# VDC.net
KiCad netlist of a schematic drawn in EAGLE
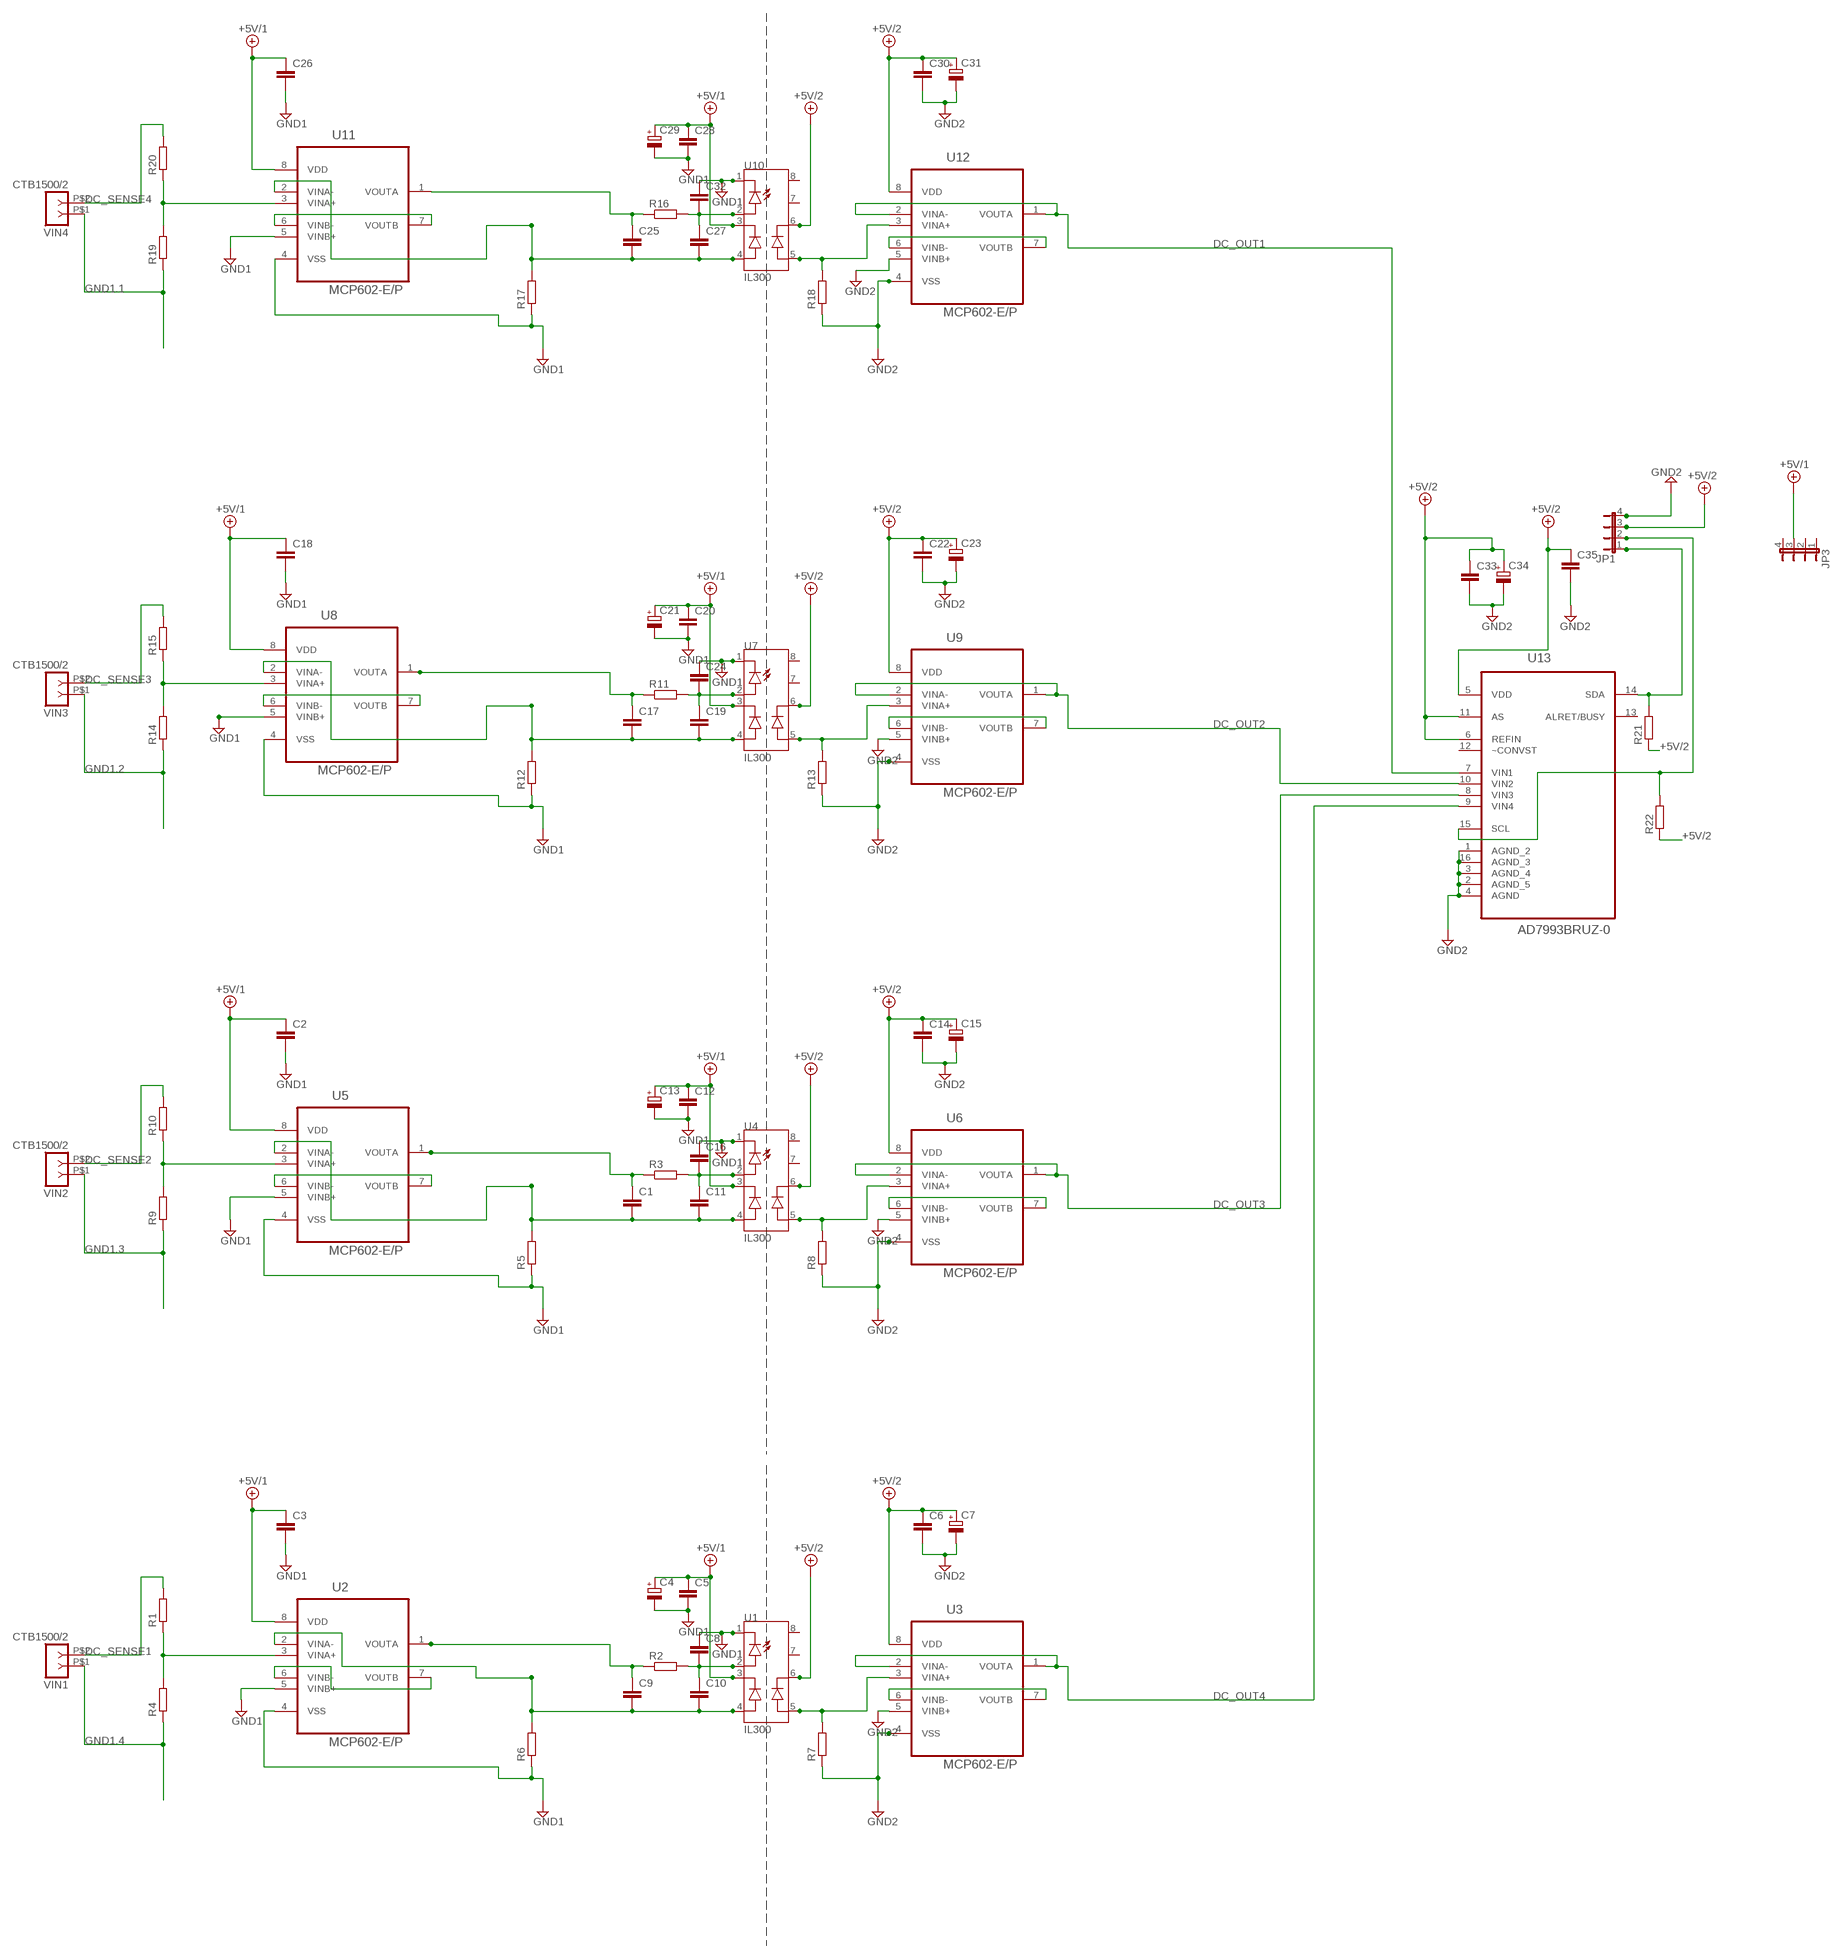
[diagram p0: schematic, sheet 1]

(export (version "E")
  (design (tool "Eeschema 10.0.6"))
  (components
    (comp (ref "C1")
      (value "C-EU025-040X050")
      (footprint "eagle-import:C025-040X050")
      (libsource (lib "eagle-import") (part "C-EU025-040X050"))
    )
    (comp (ref "C2")
      (value "C-EU025-040X050")
      (footprint "eagle-import:C025-040X050")
      (libsource (lib "eagle-import") (part "C-EU025-040X050"))
    )
    (comp (ref "C3")
      (value "C-EU025-040X050")
      (footprint "eagle-import:C025-040X050")
      (libsource (lib "eagle-import") (part "C-EU025-040X050"))
    )
    (comp (ref "C4")
      (value "CPOL-EUE2-5")
      (footprint "eagle-import:E2-5")
      (libsource (lib "eagle-import") (part "CPOL-EUE2-5"))
    )
    (comp (ref "C5")
      (value "C-EU025-040X050")
      (footprint "eagle-import:C025-040X050")
      (libsource (lib "eagle-import") (part "C-EU025-040X050"))
    )
    (comp (ref "C6")
      (value "C-EU025-040X050")
      (footprint "eagle-import:C025-040X050")
      (libsource (lib "eagle-import") (part "C-EU025-040X050"))
    )
    (comp (ref "C7")
      (value "CPOL-EUE2-5")
      (footprint "eagle-import:E2-5")
      (libsource (lib "eagle-import") (part "CPOL-EUE2-5"))
    )
    (comp (ref "C8")
      (value "C-EU025-040X050")
      (footprint "eagle-import:C025-040X050")
      (libsource (lib "eagle-import") (part "C-EU025-040X050"))
    )
    (comp (ref "C9")
      (value "C-EU025-040X050")
      (footprint "eagle-import:C025-040X050")
      (libsource (lib "eagle-import") (part "C-EU025-040X050"))
    )
    (comp (ref "C10")
      (value "C-EU025-040X050")
      (footprint "eagle-import:C025-040X050")
      (libsource (lib "eagle-import") (part "C-EU025-040X050"))
    )
    (comp (ref "C11")
      (value "C-EU025-040X050")
      (footprint "eagle-import:C025-040X050")
      (libsource (lib "eagle-import") (part "C-EU025-040X050"))
    )
    (comp (ref "C12")
      (value "C-EU025-040X050")
      (footprint "eagle-import:C025-040X050")
      (libsource (lib "eagle-import") (part "C-EU025-040X050"))
    )
    (comp (ref "C13")
      (value "CPOL-EUE2-5")
      (footprint "eagle-import:E2-5")
      (libsource (lib "eagle-import") (part "CPOL-EUE2-5"))
    )
    (comp (ref "C14")
      (value "C-EU025-040X050")
      (footprint "eagle-import:C025-040X050")
      (libsource (lib "eagle-import") (part "C-EU025-040X050"))
    )
    (comp (ref "C15")
      (value "CPOL-EUE2-5")
      (footprint "eagle-import:E2-5")
      (libsource (lib "eagle-import") (part "CPOL-EUE2-5"))
    )
    (comp (ref "C16")
      (value "C-EU025-040X050")
      (footprint "eagle-import:C025-040X050")
      (libsource (lib "eagle-import") (part "C-EU025-040X050"))
    )
    (comp (ref "C17")
      (value "C-EU025-040X050")
      (footprint "eagle-import:C025-040X050")
      (libsource (lib "eagle-import") (part "C-EU025-040X050"))
    )
    (comp (ref "C18")
      (value "C-EU025-040X050")
      (footprint "eagle-import:C025-040X050")
      (libsource (lib "eagle-import") (part "C-EU025-040X050"))
    )
    (comp (ref "C19")
      (value "C-EU025-040X050")
      (footprint "eagle-import:C025-040X050")
      (libsource (lib "eagle-import") (part "C-EU025-040X050"))
    )
    (comp (ref "C20")
      (value "C-EU025-040X050")
      (footprint "eagle-import:C025-040X050")
      (libsource (lib "eagle-import") (part "C-EU025-040X050"))
    )
    (comp (ref "C21")
      (value "CPOL-EUE2-5")
      (footprint "eagle-import:E2-5")
      (libsource (lib "eagle-import") (part "CPOL-EUE2-5"))
    )
    (comp (ref "C22")
      (value "C-EU025-040X050")
      (footprint "eagle-import:C025-040X050")
      (libsource (lib "eagle-import") (part "C-EU025-040X050"))
    )
    (comp (ref "C23")
      (value "CPOL-EUE2-5")
      (footprint "eagle-import:E2-5")
      (libsource (lib "eagle-import") (part "CPOL-EUE2-5"))
    )
    (comp (ref "C24")
      (value "C-EU025-040X050")
      (footprint "eagle-import:C025-040X050")
      (libsource (lib "eagle-import") (part "C-EU025-040X050"))
    )
    (comp (ref "C25")
      (value "C-EU025-040X050")
      (footprint "eagle-import:C025-040X050")
      (libsource (lib "eagle-import") (part "C-EU025-040X050"))
    )
    (comp (ref "C26")
      (value "C-EU025-040X050")
      (footprint "eagle-import:C025-040X050")
      (libsource (lib "eagle-import") (part "C-EU025-040X050"))
    )
    (comp (ref "C27")
      (value "C-EU025-040X050")
      (footprint "eagle-import:C025-040X050")
      (libsource (lib "eagle-import") (part "C-EU025-040X050"))
    )
    (comp (ref "C28")
      (value "C-EU025-040X050")
      (footprint "eagle-import:C025-040X050")
      (libsource (lib "eagle-import") (part "C-EU025-040X050"))
    )
    (comp (ref "C29")
      (value "CPOL-EUE2-5")
      (footprint "eagle-import:E2-5")
      (libsource (lib "eagle-import") (part "CPOL-EUE2-5"))
    )
    (comp (ref "C30")
      (value "C-EU025-040X050")
      (footprint "eagle-import:C025-040X050")
      (libsource (lib "eagle-import") (part "C-EU025-040X050"))
    )
    (comp (ref "C31")
      (value "CPOL-EUE2-5")
      (footprint "eagle-import:E2-5")
      (libsource (lib "eagle-import") (part "CPOL-EUE2-5"))
    )
    (comp (ref "C32")
      (value "C-EU025-040X050")
      (footprint "eagle-import:C025-040X050")
      (libsource (lib "eagle-import") (part "C-EU025-040X050"))
    )
    (comp (ref "C33")
      (value "C-EU025-024X044")
      (footprint "eagle-import:C025-024X044")
      (libsource (lib "eagle-import") (part "C-EU025-024X044"))
    )
    (comp (ref "C34")
      (value "CPOL-EUE2-4")
      (footprint "eagle-import:E2-4")
      (libsource (lib "eagle-import") (part "CPOL-EUE2-4"))
    )
    (comp (ref "C35")
      (value "C-EU025-025X050")
      (footprint "eagle-import:C025-025X050")
      (libsource (lib "eagle-import") (part "C-EU025-025X050"))
    )
    (comp (ref "JP1")
      (value "JP4E")
      (footprint "eagle-import:JP4")
      (libsource (lib "eagle-import") (part "JP4E"))
    )
    (comp (ref "JP3")
      (value "JP4E")
      (footprint "eagle-import:JP4")
      (libsource (lib "eagle-import") (part "JP4E"))
    )
    (comp (ref "R1")
      (value "R-EU_0207/10")
      (footprint "eagle-import:0207_10")
      (libsource (lib "eagle-import") (part "R-EU_0207/10"))
    )
    (comp (ref "R2")
      (value "R-EU_0207/10")
      (footprint "eagle-import:0207_10")
      (libsource (lib "eagle-import") (part "R-EU_0207/10"))
    )
    (comp (ref "R3")
      (value "R-EU_0207/10")
      (footprint "eagle-import:0207_10")
      (libsource (lib "eagle-import") (part "R-EU_0207/10"))
    )
    (comp (ref "R4")
      (value "R-EU_0207/10")
      (footprint "eagle-import:0207_10")
      (libsource (lib "eagle-import") (part "R-EU_0207/10"))
    )
    (comp (ref "R5")
      (value "R-EU_0207/10")
      (footprint "eagle-import:0207_10")
      (libsource (lib "eagle-import") (part "R-EU_0207/10"))
    )
    (comp (ref "R6")
      (value "R-EU_0207/10")
      (footprint "eagle-import:0207_10")
      (libsource (lib "eagle-import") (part "R-EU_0207/10"))
    )
    (comp (ref "R7")
      (value "R-EU_0207/10")
      (footprint "eagle-import:0207_10")
      (libsource (lib "eagle-import") (part "R-EU_0207/10"))
    )
    (comp (ref "R8")
      (value "R-EU_0207/10")
      (footprint "eagle-import:0207_10")
      (libsource (lib "eagle-import") (part "R-EU_0207/10"))
    )
    (comp (ref "R9")
      (value "R-EU_0207/10")
      (footprint "eagle-import:0207_10")
      (libsource (lib "eagle-import") (part "R-EU_0207/10"))
    )
    (comp (ref "R10")
      (value "R-EU_0207/10")
      (footprint "eagle-import:0207_10")
      (libsource (lib "eagle-import") (part "R-EU_0207/10"))
    )
    (comp (ref "R11")
      (value "R-EU_0207/10")
      (footprint "eagle-import:0207_10")
      (libsource (lib "eagle-import") (part "R-EU_0207/10"))
    )
    (comp (ref "R12")
      (value "R-EU_0207/10")
      (footprint "eagle-import:0207_10")
      (libsource (lib "eagle-import") (part "R-EU_0207/10"))
    )
    (comp (ref "R13")
      (value "R-EU_0207/10")
      (footprint "eagle-import:0207_10")
      (libsource (lib "eagle-import") (part "R-EU_0207/10"))
    )
    (comp (ref "R14")
      (value "R-EU_0207/10")
      (footprint "eagle-import:0207_10")
      (libsource (lib "eagle-import") (part "R-EU_0207/10"))
    )
    (comp (ref "R15")
      (value "R-EU_0207/10")
      (footprint "eagle-import:0207_10")
      (libsource (lib "eagle-import") (part "R-EU_0207/10"))
    )
    (comp (ref "R16")
      (value "R-EU_0207/10")
      (footprint "eagle-import:0207_10")
      (libsource (lib "eagle-import") (part "R-EU_0207/10"))
    )
    (comp (ref "R17")
      (value "R-EU_0207/10")
      (footprint "eagle-import:0207_10")
      (libsource (lib "eagle-import") (part "R-EU_0207/10"))
    )
    (comp (ref "R18")
      (value "R-EU_0207/10")
      (footprint "eagle-import:0207_10")
      (libsource (lib "eagle-import") (part "R-EU_0207/10"))
    )
    (comp (ref "R19")
      (value "R-EU_0207/10")
      (footprint "eagle-import:0207_10")
      (libsource (lib "eagle-import") (part "R-EU_0207/10"))
    )
    (comp (ref "R20")
      (value "R-EU_0207/10")
      (footprint "eagle-import:0207_10")
      (libsource (lib "eagle-import") (part "R-EU_0207/10"))
    )
    (comp (ref "R21")
      (value "R-EU_0207/10")
      (footprint "eagle-import:0207_10")
      (libsource (lib "eagle-import") (part "R-EU_0207/10"))
    )
    (comp (ref "R22")
      (value "R-EU_0207/10")
      (footprint "eagle-import:0207_10")
      (libsource (lib "eagle-import") (part "R-EU_0207/10"))
    )
    (comp (ref "U1")
      (value "IL300")
      (footprint "eagle-import:DIL08")
      (libsource (lib "eagle-import") (part "IL300"))
    )
    (comp (ref "U2")
      (value "MCP602-E/P")
      (footprint "eagle-import:DIP254P762X508-8P")
      (libsource (lib "eagle-import") (part "MCP602-E/P"))
    )
    (comp (ref "U3")
      (value "MCP602-E/P")
      (footprint "eagle-import:DIP254P762X508-8P")
      (libsource (lib "eagle-import") (part "MCP602-E/P"))
    )
    (comp (ref "U4")
      (value "IL300")
      (footprint "eagle-import:DIL08")
      (libsource (lib "eagle-import") (part "IL300"))
    )
    (comp (ref "U5")
      (value "MCP602-E/P")
      (footprint "eagle-import:DIP254P762X508-8P")
      (libsource (lib "eagle-import") (part "MCP602-E/P"))
    )
    (comp (ref "U6")
      (value "MCP602-E/P")
      (footprint "eagle-import:DIP254P762X508-8P")
      (libsource (lib "eagle-import") (part "MCP602-E/P"))
    )
    (comp (ref "U7")
      (value "IL300")
      (footprint "eagle-import:DIL08")
      (libsource (lib "eagle-import") (part "IL300"))
    )
    (comp (ref "U8")
      (value "MCP602-E/P")
      (footprint "eagle-import:DIP254P762X508-8P")
      (libsource (lib "eagle-import") (part "MCP602-E/P"))
    )
    (comp (ref "U9")
      (value "MCP602-E/P")
      (footprint "eagle-import:DIP254P762X508-8P")
      (libsource (lib "eagle-import") (part "MCP602-E/P"))
    )
    (comp (ref "U10")
      (value "IL300")
      (footprint "eagle-import:DIL08")
      (libsource (lib "eagle-import") (part "IL300"))
    )
    (comp (ref "U11")
      (value "MCP602-E/P")
      (footprint "eagle-import:DIP254P762X508-8P")
      (libsource (lib "eagle-import") (part "MCP602-E/P"))
    )
    (comp (ref "U12")
      (value "MCP602-E/P")
      (footprint "eagle-import:DIP254P762X508-8P")
      (libsource (lib "eagle-import") (part "MCP602-E/P"))
    )
    (comp (ref "U13")
      (value "AD7993BRUZ-0")
      (footprint "eagle-import:SOP65P640X120-16N")
      (libsource (lib "eagle-import") (part "AD7993BRUZ-0"))
    )
    (comp (ref "VIN1")
      (value "CTB1500/2")
      (footprint "eagle-import:CTB1500-2")
      (libsource (lib "eagle-import") (part "CTB1500/2"))
    )
    (comp (ref "VIN2")
      (value "CTB1500/2")
      (footprint "eagle-import:CTB1500-2")
      (libsource (lib "eagle-import") (part "CTB1500/2"))
    )
    (comp (ref "VIN3")
      (value "CTB1500/2")
      (footprint "eagle-import:CTB1500-2")
      (libsource (lib "eagle-import") (part "CTB1500/2"))
    )
    (comp (ref "VIN4")
      (value "CTB1500/2")
      (footprint "eagle-import:CTB1500-2")
      (libsource (lib "eagle-import") (part "CTB1500/2"))
    )
  )
  (nets
    (net (code "1") (name "+5V{slash}1") (class "Default")
      (node (ref "C12") (pin "1") (pinfunction "1_1") (pintype "passive"))
      (node (ref "C13") (pin "+") (pinfunction "+_+") (pintype "passive"))
      (node (ref "C18") (pin "1") (pinfunction "1_1") (pintype "passive"))
      (node (ref "C2") (pin "1") (pinfunction "1_1") (pintype "passive"))
      (node (ref "C20") (pin "1") (pinfunction "1_1") (pintype "passive"))
      (node (ref "C21") (pin "+") (pinfunction "+_+") (pintype "passive"))
      (node (ref "C26") (pin "1") (pinfunction "1_1") (pintype "passive"))
      (node (ref "C28") (pin "1") (pinfunction "1_1") (pintype "passive"))
      (node (ref "C29") (pin "+") (pinfunction "+_+") (pintype "passive"))
      (node (ref "C3") (pin "1") (pinfunction "1_1") (pintype "passive"))
      (node (ref "C4") (pin "+") (pinfunction "+_+") (pintype "passive"))
      (node (ref "C5") (pin "1") (pinfunction "1_1") (pintype "passive"))
      (node (ref "JP3") (pin "3") (pinfunction "3_3") (pintype "passive"))
      (node (ref "U1") (pin "3") (pinfunction "C_FB_3") (pintype "passive"))
      (node (ref "U10") (pin "3") (pinfunction "C_FB_3") (pintype "passive"))
      (node (ref "U11") (pin "8") (pinfunction "VDD_8") (pintype "power_in"))
      (node (ref "U2") (pin "8") (pinfunction "VDD_8") (pintype "power_in"))
      (node (ref "U4") (pin "3") (pinfunction "C_FB_3") (pintype "passive"))
      (node (ref "U5") (pin "8") (pinfunction "VDD_8") (pintype "power_in"))
      (node (ref "U7") (pin "3") (pinfunction "C_FB_3") (pintype "passive"))
      (node (ref "U8") (pin "8") (pinfunction "VDD_8") (pintype "power_in"))
    )
    (net (code "2") (name "+5V{slash}2") (class "Default")
      (node (ref "C14") (pin "1") (pinfunction "1_1") (pintype "passive"))
      (node (ref "C15") (pin "+") (pinfunction "+_+") (pintype "passive"))
      (node (ref "C22") (pin "1") (pinfunction "1_1") (pintype "passive"))
      (node (ref "C23") (pin "+") (pinfunction "+_+") (pintype "passive"))
      (node (ref "C30") (pin "1") (pinfunction "1_1") (pintype "passive"))
      (node (ref "C31") (pin "+") (pinfunction "+_+") (pintype "passive"))
      (node (ref "C33") (pin "1") (pinfunction "1_1") (pintype "passive"))
      (node (ref "C34") (pin "+") (pinfunction "+_+") (pintype "passive"))
      (node (ref "C35") (pin "1") (pinfunction "1_1") (pintype "passive"))
      (node (ref "C6") (pin "1") (pinfunction "1_1") (pintype "passive"))
      (node (ref "C7") (pin "+") (pinfunction "+_+") (pintype "passive"))
      (node (ref "JP1") (pin "3") (pinfunction "3_3") (pintype "passive"))
      (node (ref "R21") (pin "1") (pinfunction "1_1") (pintype "passive"))
      (node (ref "R22") (pin "1") (pinfunction "1_1") (pintype "passive"))
      (node (ref "U1") (pin "6") (pinfunction "C_OUT_6") (pintype "passive"))
      (node (ref "U10") (pin "6") (pinfunction "C_OUT_6") (pintype "passive"))
      (node (ref "U12") (pin "8") (pinfunction "VDD_8") (pintype "power_in"))
      (node (ref "U13") (pin "11") (pinfunction "AS_11") (pintype "input"))
      (node (ref "U13") (pin "5") (pinfunction "VDD_5") (pintype "power_in"))
      (node (ref "U13") (pin "6") (pinfunction "REFIN_6") (pintype "input"))
      (node (ref "U3") (pin "8") (pinfunction "VDD_8") (pintype "power_in"))
      (node (ref "U4") (pin "6") (pinfunction "C_OUT_6") (pintype "passive"))
      (node (ref "U6") (pin "8") (pinfunction "VDD_8") (pintype "power_in"))
      (node (ref "U7") (pin "6") (pinfunction "C_OUT_6") (pintype "passive"))
      (node (ref "U9") (pin "8") (pinfunction "VDD_8") (pintype "power_in"))
    )
    (net (code "3") (name "/DC_OUT1") (class "Default")
      (node (ref "U12") (pin "1") (pinfunction "VOUTA_1") (pintype "output"))
      (node (ref "U12") (pin "2") (pinfunction "VINA-_2") (pintype "input"))
      (node (ref "U13") (pin "7") (pinfunction "VIN1_7") (pintype "input"))
    )
    (net (code "4") (name "/DC_OUT2") (class "Default")
      (node (ref "U13") (pin "10") (pinfunction "VIN2_10") (pintype "input"))
      (node (ref "U9") (pin "1") (pinfunction "VOUTA_1") (pintype "output"))
      (node (ref "U9") (pin "2") (pinfunction "VINA-_2") (pintype "input"))
    )
    (net (code "5") (name "/DC_OUT3") (class "Default")
      (node (ref "U13") (pin "8") (pinfunction "VIN3_8") (pintype "input"))
      (node (ref "U6") (pin "1") (pinfunction "VOUTA_1") (pintype "output"))
      (node (ref "U6") (pin "2") (pinfunction "VINA-_2") (pintype "input"))
    )
    (net (code "6") (name "/DC_OUT4") (class "Default")
      (node (ref "U13") (pin "9") (pinfunction "VIN4_9") (pintype "input"))
      (node (ref "U3") (pin "1") (pinfunction "VOUTA_1") (pintype "output"))
      (node (ref "U3") (pin "2") (pinfunction "VINA-_2") (pintype "input"))
    )
    (net (code "7") (name "/DC_SENSE1") (class "Default")
      (node (ref "R1") (pin "2") (pinfunction "2_2") (pintype "passive"))
      (node (ref "VIN1") (pin "P$2") (pinfunction "2_P$2") (pintype "passive"))
    )
    (net (code "8") (name "/DC_SENSE2") (class "Default")
      (node (ref "R10") (pin "2") (pinfunction "2_2") (pintype "passive"))
      (node (ref "VIN2") (pin "P$2") (pinfunction "2_P$2") (pintype "passive"))
    )
    (net (code "9") (name "/DC_SENSE3") (class "Default")
      (node (ref "R15") (pin "2") (pinfunction "2_2") (pintype "passive"))
      (node (ref "VIN3") (pin "P$2") (pinfunction "2_P$2") (pintype "passive"))
    )
    (net (code "10") (name "/DC_SENSE4") (class "Default")
      (node (ref "R20") (pin "2") (pinfunction "2_2") (pintype "passive"))
      (node (ref "VIN4") (pin "P$2") (pinfunction "2_P$2") (pintype "passive"))
    )
    (net (code "11") (name "/GND1.1") (class "Default")
      (node (ref "R19") (pin "1") (pinfunction "1_1") (pintype "passive"))
      (node (ref "VIN4") (pin "P$1") (pinfunction "1_P$1") (pintype "passive"))
    )
    (net (code "12") (name "/GND1.2") (class "Default")
      (node (ref "R14") (pin "1") (pinfunction "1_1") (pintype "passive"))
      (node (ref "VIN3") (pin "P$1") (pinfunction "1_P$1") (pintype "passive"))
    )
    (net (code "13") (name "/GND1.3") (class "Default")
      (node (ref "R9") (pin "1") (pinfunction "1_1") (pintype "passive"))
      (node (ref "VIN2") (pin "P$1") (pinfunction "1_P$1") (pintype "passive"))
    )
    (net (code "14") (name "/GND1.4") (class "Default")
      (node (ref "R4") (pin "1") (pinfunction "1_1") (pintype "passive"))
      (node (ref "VIN1") (pin "P$1") (pinfunction "1_P$1") (pintype "passive"))
    )
    (net (code "15") (name "GND1") (class "Default")
      (node (ref "C12") (pin "2") (pinfunction "2_2") (pintype "passive"))
      (node (ref "C13") (pin "-") (pinfunction "-_-") (pintype "passive"))
      (node (ref "C16") (pin "1") (pinfunction "1_1") (pintype "passive"))
      (node (ref "C18") (pin "2") (pinfunction "2_2") (pintype "passive"))
      (node (ref "C2") (pin "2") (pinfunction "2_2") (pintype "passive"))
      (node (ref "C20") (pin "2") (pinfunction "2_2") (pintype "passive"))
      (node (ref "C21") (pin "-") (pinfunction "-_-") (pintype "passive"))
      (node (ref "C24") (pin "1") (pinfunction "1_1") (pintype "passive"))
      (node (ref "C26") (pin "2") (pinfunction "2_2") (pintype "passive"))
      (node (ref "C28") (pin "2") (pinfunction "2_2") (pintype "passive"))
      (node (ref "C29") (pin "-") (pinfunction "-_-") (pintype "passive"))
      (node (ref "C3") (pin "2") (pinfunction "2_2") (pintype "passive"))
      (node (ref "C32") (pin "1") (pinfunction "1_1") (pintype "passive"))
      (node (ref "C4") (pin "-") (pinfunction "-_-") (pintype "passive"))
      (node (ref "C5") (pin "2") (pinfunction "2_2") (pintype "passive"))
      (node (ref "C8") (pin "1") (pinfunction "1_1") (pintype "passive"))
      (node (ref "R12") (pin "1") (pinfunction "1_1") (pintype "passive"))
      (node (ref "R17") (pin "1") (pinfunction "1_1") (pintype "passive"))
      (node (ref "R5") (pin "1") (pinfunction "1_1") (pintype "passive"))
      (node (ref "R6") (pin "1") (pinfunction "1_1") (pintype "passive"))
      (node (ref "U1") (pin "1") (pinfunction "C_LED_1") (pintype "passive"))
      (node (ref "U10") (pin "1") (pinfunction "C_LED_1") (pintype "passive"))
      (node (ref "U11") (pin "4") (pinfunction "VSS_4") (pintype "power_in"))
      (node (ref "U11") (pin "5") (pinfunction "VINB+_5") (pintype "input"))
      (node (ref "U2") (pin "4") (pinfunction "VSS_4") (pintype "power_in"))
      (node (ref "U2") (pin "5") (pinfunction "VINB+_5") (pintype "input"))
      (node (ref "U4") (pin "1") (pinfunction "C_LED_1") (pintype "passive"))
      (node (ref "U5") (pin "4") (pinfunction "VSS_4") (pintype "power_in"))
      (node (ref "U5") (pin "5") (pinfunction "VINB+_5") (pintype "input"))
      (node (ref "U7") (pin "1") (pinfunction "C_LED_1") (pintype "passive"))
      (node (ref "U8") (pin "4") (pinfunction "VSS_4") (pintype "power_in"))
      (node (ref "U8") (pin "5") (pinfunction "VINB+_5") (pintype "input"))
    )
    (net (code "16") (name "GND2") (class "Default")
      (node (ref "C14") (pin "2") (pinfunction "2_2") (pintype "passive"))
      (node (ref "C15") (pin "-") (pinfunction "-_-") (pintype "passive"))
      (node (ref "C22") (pin "2") (pinfunction "2_2") (pintype "passive"))
      (node (ref "C23") (pin "-") (pinfunction "-_-") (pintype "passive"))
      (node (ref "C30") (pin "2") (pinfunction "2_2") (pintype "passive"))
      (node (ref "C31") (pin "-") (pinfunction "-_-") (pintype "passive"))
      (node (ref "C33") (pin "2") (pinfunction "2_2") (pintype "passive"))
      (node (ref "C34") (pin "-") (pinfunction "-_-") (pintype "passive"))
      (node (ref "C35") (pin "2") (pinfunction "2_2") (pintype "passive"))
      (node (ref "C6") (pin "2") (pinfunction "2_2") (pintype "passive"))
      (node (ref "C7") (pin "-") (pinfunction "-_-") (pintype "passive"))
      (node (ref "JP1") (pin "4") (pinfunction "4_4") (pintype "passive"))
      (node (ref "R13") (pin "1") (pinfunction "1_1") (pintype "passive"))
      (node (ref "R18") (pin "1") (pinfunction "1_1") (pintype "passive"))
      (node (ref "R7") (pin "1") (pinfunction "1_1") (pintype "passive"))
      (node (ref "R8") (pin "1") (pinfunction "1_1") (pintype "passive"))
      (node (ref "U12") (pin "4") (pinfunction "VSS_4") (pintype "power_in"))
      (node (ref "U12") (pin "5") (pinfunction "VINB+_5") (pintype "input"))
      (node (ref "U13") (pin "1") (pinfunction "AGND_2_1") (pintype "passive"))
      (node (ref "U13") (pin "16") (pinfunction "AGND_3_16") (pintype "passive"))
      (node (ref "U13") (pin "2") (pinfunction "AGND_5_2") (pintype "passive"))
      (node (ref "U13") (pin "3") (pinfunction "AGND_4_3") (pintype "passive"))
      (node (ref "U13") (pin "4") (pinfunction "AGND_4") (pintype "passive"))
      (node (ref "U3") (pin "4") (pinfunction "VSS_4") (pintype "power_in"))
      (node (ref "U3") (pin "5") (pinfunction "VINB+_5") (pintype "input"))
      (node (ref "U6") (pin "4") (pinfunction "VSS_4") (pintype "power_in"))
      (node (ref "U6") (pin "5") (pinfunction "VINB+_5") (pintype "input"))
      (node (ref "U9") (pin "4") (pinfunction "VSS_4") (pintype "power_in"))
      (node (ref "U9") (pin "5") (pinfunction "VINB+_5") (pintype "input"))
    )
    (net (code "17") (name "Net-(U1-A_FB)") (class "Default")
      (node (ref "C10") (pin "2") (pinfunction "2_2") (pintype "passive"))
      (node (ref "C9") (pin "2") (pinfunction "2_2") (pintype "passive"))
      (node (ref "R6") (pin "2") (pinfunction "2_2") (pintype "passive"))
      (node (ref "U1") (pin "4") (pinfunction "A_FB_4") (pintype "passive"))
      (node (ref "U2") (pin "2") (pinfunction "VINA-_2") (pintype "input"))
    )
    (net (code "18") (name "Net-(U1-A_LED)") (class "Default")
      (node (ref "C10") (pin "1") (pinfunction "1_1") (pintype "passive"))
      (node (ref "C8") (pin "2") (pinfunction "2_2") (pintype "passive"))
      (node (ref "R2") (pin "2") (pinfunction "2_2") (pintype "passive"))
      (node (ref "U1") (pin "2") (pinfunction "A_LED_2") (pintype "passive"))
    )
    (net (code "19") (name "Net-(U1-A_OUT)") (class "Default")
      (node (ref "R7") (pin "2") (pinfunction "2_2") (pintype "passive"))
      (node (ref "U1") (pin "5") (pinfunction "A_OUT_5") (pintype "passive"))
      (node (ref "U3") (pin "3") (pinfunction "VINA+_3") (pintype "input"))
    )
    (net (code "20") (name "Net-(U2-VINA+)") (class "Default")
      (node (ref "R1") (pin "1") (pinfunction "1_1") (pintype "passive"))
      (node (ref "R4") (pin "2") (pinfunction "2_2") (pintype "passive"))
      (node (ref "U2") (pin "3") (pinfunction "VINA+_3") (pintype "input"))
    )
    (net (code "21") (name "Net-(U2-VINB-)") (class "Default")
      (node (ref "U2") (pin "6") (pinfunction "VINB-_6") (pintype "input"))
      (node (ref "U2") (pin "7") (pinfunction "VOUTB_7") (pintype "output"))
    )
    (net (code "22") (name "Net-(U2-VOUTA)") (class "Default")
      (node (ref "C9") (pin "1") (pinfunction "1_1") (pintype "passive"))
      (node (ref "R2") (pin "1") (pinfunction "1_1") (pintype "passive"))
      (node (ref "U2") (pin "1") (pinfunction "VOUTA_1") (pintype "output"))
    )
    (net (code "23") (name "Net-(U3-VINB-)") (class "Default")
      (node (ref "U3") (pin "6") (pinfunction "VINB-_6") (pintype "input"))
      (node (ref "U3") (pin "7") (pinfunction "VOUTB_7") (pintype "output"))
    )
    (net (code "24") (name "Net-(U4-A_FB)") (class "Default")
      (node (ref "C1") (pin "2") (pinfunction "2_2") (pintype "passive"))
      (node (ref "C11") (pin "2") (pinfunction "2_2") (pintype "passive"))
      (node (ref "R5") (pin "2") (pinfunction "2_2") (pintype "passive"))
      (node (ref "U4") (pin "4") (pinfunction "A_FB_4") (pintype "passive"))
      (node (ref "U5") (pin "2") (pinfunction "VINA-_2") (pintype "input"))
    )
    (net (code "25") (name "Net-(U4-A_LED)") (class "Default")
      (node (ref "C11") (pin "1") (pinfunction "1_1") (pintype "passive"))
      (node (ref "C16") (pin "2") (pinfunction "2_2") (pintype "passive"))
      (node (ref "R3") (pin "2") (pinfunction "2_2") (pintype "passive"))
      (node (ref "U4") (pin "2") (pinfunction "A_LED_2") (pintype "passive"))
    )
    (net (code "26") (name "Net-(U4-A_OUT)") (class "Default")
      (node (ref "R8") (pin "2") (pinfunction "2_2") (pintype "passive"))
      (node (ref "U4") (pin "5") (pinfunction "A_OUT_5") (pintype "passive"))
      (node (ref "U6") (pin "3") (pinfunction "VINA+_3") (pintype "input"))
    )
    (net (code "27") (name "Net-(U5-VINA+)") (class "Default")
      (node (ref "R10") (pin "1") (pinfunction "1_1") (pintype "passive"))
      (node (ref "R9") (pin "2") (pinfunction "2_2") (pintype "passive"))
      (node (ref "U5") (pin "3") (pinfunction "VINA+_3") (pintype "input"))
    )
    (net (code "28") (name "Net-(U5-VINB-)") (class "Default")
      (node (ref "U5") (pin "6") (pinfunction "VINB-_6") (pintype "input"))
      (node (ref "U5") (pin "7") (pinfunction "VOUTB_7") (pintype "output"))
    )
    (net (code "29") (name "Net-(U5-VOUTA)") (class "Default")
      (node (ref "C1") (pin "1") (pinfunction "1_1") (pintype "passive"))
      (node (ref "R3") (pin "1") (pinfunction "1_1") (pintype "passive"))
      (node (ref "U5") (pin "1") (pinfunction "VOUTA_1") (pintype "output"))
    )
    (net (code "30") (name "Net-(U6-VINB-)") (class "Default")
      (node (ref "U6") (pin "6") (pinfunction "VINB-_6") (pintype "input"))
      (node (ref "U6") (pin "7") (pinfunction "VOUTB_7") (pintype "output"))
    )
    (net (code "31") (name "Net-(U7-A_FB)") (class "Default")
      (node (ref "C17") (pin "2") (pinfunction "2_2") (pintype "passive"))
      (node (ref "C19") (pin "2") (pinfunction "2_2") (pintype "passive"))
      (node (ref "R12") (pin "2") (pinfunction "2_2") (pintype "passive"))
      (node (ref "U7") (pin "4") (pinfunction "A_FB_4") (pintype "passive"))
      (node (ref "U8") (pin "2") (pinfunction "VINA-_2") (pintype "input"))
    )
    (net (code "32") (name "Net-(U7-A_LED)") (class "Default")
      (node (ref "C19") (pin "1") (pinfunction "1_1") (pintype "passive"))
      (node (ref "C24") (pin "2") (pinfunction "2_2") (pintype "passive"))
      (node (ref "R11") (pin "2") (pinfunction "2_2") (pintype "passive"))
      (node (ref "U7") (pin "2") (pinfunction "A_LED_2") (pintype "passive"))
    )
    (net (code "33") (name "Net-(U7-A_OUT)") (class "Default")
      (node (ref "R13") (pin "2") (pinfunction "2_2") (pintype "passive"))
      (node (ref "U7") (pin "5") (pinfunction "A_OUT_5") (pintype "passive"))
      (node (ref "U9") (pin "3") (pinfunction "VINA+_3") (pintype "input"))
    )
    (net (code "34") (name "Net-(U8-VINA+)") (class "Default")
      (node (ref "R14") (pin "2") (pinfunction "2_2") (pintype "passive"))
      (node (ref "R15") (pin "1") (pinfunction "1_1") (pintype "passive"))
      (node (ref "U8") (pin "3") (pinfunction "VINA+_3") (pintype "input"))
    )
    (net (code "35") (name "Net-(U8-VINB-)") (class "Default")
      (node (ref "U8") (pin "6") (pinfunction "VINB-_6") (pintype "input"))
      (node (ref "U8") (pin "7") (pinfunction "VOUTB_7") (pintype "output"))
    )
    (net (code "36") (name "Net-(U8-VOUTA)") (class "Default")
      (node (ref "C17") (pin "1") (pinfunction "1_1") (pintype "passive"))
      (node (ref "R11") (pin "1") (pinfunction "1_1") (pintype "passive"))
      (node (ref "U8") (pin "1") (pinfunction "VOUTA_1") (pintype "output"))
    )
    (net (code "37") (name "Net-(U9-VINB-)") (class "Default")
      (node (ref "U9") (pin "6") (pinfunction "VINB-_6") (pintype "input"))
      (node (ref "U9") (pin "7") (pinfunction "VOUTB_7") (pintype "output"))
    )
    (net (code "38") (name "Net-(U10-A_FB)") (class "Default")
      (node (ref "C25") (pin "2") (pinfunction "2_2") (pintype "passive"))
      (node (ref "C27") (pin "2") (pinfunction "2_2") (pintype "passive"))
      (node (ref "R17") (pin "2") (pinfunction "2_2") (pintype "passive"))
      (node (ref "U10") (pin "4") (pinfunction "A_FB_4") (pintype "passive"))
      (node (ref "U11") (pin "2") (pinfunction "VINA-_2") (pintype "input"))
    )
    (net (code "39") (name "Net-(U10-A_LED)") (class "Default")
      (node (ref "C27") (pin "1") (pinfunction "1_1") (pintype "passive"))
      (node (ref "C32") (pin "2") (pinfunction "2_2") (pintype "passive"))
      (node (ref "R16") (pin "2") (pinfunction "2_2") (pintype "passive"))
      (node (ref "U10") (pin "2") (pinfunction "A_LED_2") (pintype "passive"))
    )
    (net (code "40") (name "Net-(U10-A_OUT)") (class "Default")
      (node (ref "R18") (pin "2") (pinfunction "2_2") (pintype "passive"))
      (node (ref "U10") (pin "5") (pinfunction "A_OUT_5") (pintype "passive"))
      (node (ref "U12") (pin "3") (pinfunction "VINA+_3") (pintype "input"))
    )
    (net (code "41") (name "Net-(U11-VINA+)") (class "Default")
      (node (ref "R19") (pin "2") (pinfunction "2_2") (pintype "passive"))
      (node (ref "R20") (pin "1") (pinfunction "1_1") (pintype "passive"))
      (node (ref "U11") (pin "3") (pinfunction "VINA+_3") (pintype "input"))
    )
    (net (code "42") (name "Net-(U11-VINB-)") (class "Default")
      (node (ref "U11") (pin "6") (pinfunction "VINB-_6") (pintype "input"))
      (node (ref "U11") (pin "7") (pinfunction "VOUTB_7") (pintype "output"))
    )
    (net (code "43") (name "Net-(U11-VOUTA)") (class "Default")
      (node (ref "C25") (pin "1") (pinfunction "1_1") (pintype "passive"))
      (node (ref "R16") (pin "1") (pinfunction "1_1") (pintype "passive"))
      (node (ref "U11") (pin "1") (pinfunction "VOUTA_1") (pintype "output"))
    )
    (net (code "44") (name "Net-(U12-VINB-)") (class "Default")
      (node (ref "U12") (pin "6") (pinfunction "VINB-_6") (pintype "input"))
      (node (ref "U12") (pin "7") (pinfunction "VOUTB_7") (pintype "output"))
    )
    (net (code "45") (name "Net-(U13-SCL)") (class "Default")
      (node (ref "JP1") (pin "2") (pinfunction "2_2") (pintype "passive"))
      (node (ref "R22") (pin "2") (pinfunction "2_2") (pintype "passive"))
      (node (ref "U13") (pin "15") (pinfunction "SCL_15") (pintype "input"))
    )
    (net (code "46") (name "Net-(U13-SDA)") (class "Default")
      (node (ref "JP1") (pin "1") (pinfunction "1_1") (pintype "passive"))
      (node (ref "R21") (pin "2") (pinfunction "2_2") (pintype "passive"))
      (node (ref "U13") (pin "14") (pinfunction "SDA_14") (pintype "bidirectional"))
    )
    (net (code "47") (name "unconnected-(JP3-Pad1)") (class "Default")
      (node (ref "JP3") (pin "1") (pinfunction "1_1") (pintype "passive"))
    )
    (net (code "48") (name "unconnected-(JP3-Pad2)") (class "Default")
      (node (ref "JP3") (pin "2") (pinfunction "2_2") (pintype "passive"))
    )
    (net (code "49") (name "unconnected-(JP3-Pad4)") (class "Default")
      (node (ref "JP3") (pin "4") (pinfunction "4_4") (pintype "passive"))
    )
    (net (code "50") (name "unconnected-(U1-PIN7-Pad7)") (class "Default")
      (node (ref "U1") (pin "7") (pinfunction "PIN7_7") (pintype "no_connect"))
    )
    (net (code "51") (name "unconnected-(U1-PIN8-Pad8)") (class "Default")
      (node (ref "U1") (pin "8") (pinfunction "PIN8_8") (pintype "no_connect"))
    )
    (net (code "52") (name "unconnected-(U4-PIN7-Pad7)") (class "Default")
      (node (ref "U4") (pin "7") (pinfunction "PIN7_7") (pintype "no_connect"))
    )
    (net (code "53") (name "unconnected-(U4-PIN8-Pad8)") (class "Default")
      (node (ref "U4") (pin "8") (pinfunction "PIN8_8") (pintype "no_connect"))
    )
    (net (code "54") (name "unconnected-(U7-PIN7-Pad7)") (class "Default")
      (node (ref "U7") (pin "7") (pinfunction "PIN7_7") (pintype "no_connect"))
    )
    (net (code "55") (name "unconnected-(U7-PIN8-Pad8)") (class "Default")
      (node (ref "U7") (pin "8") (pinfunction "PIN8_8") (pintype "no_connect"))
    )
    (net (code "56") (name "unconnected-(U10-PIN7-Pad7)") (class "Default")
      (node (ref "U10") (pin "7") (pinfunction "PIN7_7") (pintype "no_connect"))
    )
    (net (code "57") (name "unconnected-(U10-PIN8-Pad8)") (class "Default")
      (node (ref "U10") (pin "8") (pinfunction "PIN8_8") (pintype "no_connect"))
    )
    (net (code "58") (name "unconnected-(U13-ALRET{slash}BUSY-Pad13)") (class "Default")
      (node (ref "U13") (pin "13") (pinfunction "ALRET/BUSY_13") (pintype "output"))
    )
    (net (code "59") (name "unconnected-(U13-~{CONVST}-Pad12)") (class "Default")
      (node (ref "U13") (pin "12") (pinfunction "~{CONVST}_12") (pintype "input"))
    )
  )
)
